# mainboard_interface_v1_5.net
KiCad netlist of a schematic drawn in Altium Designer
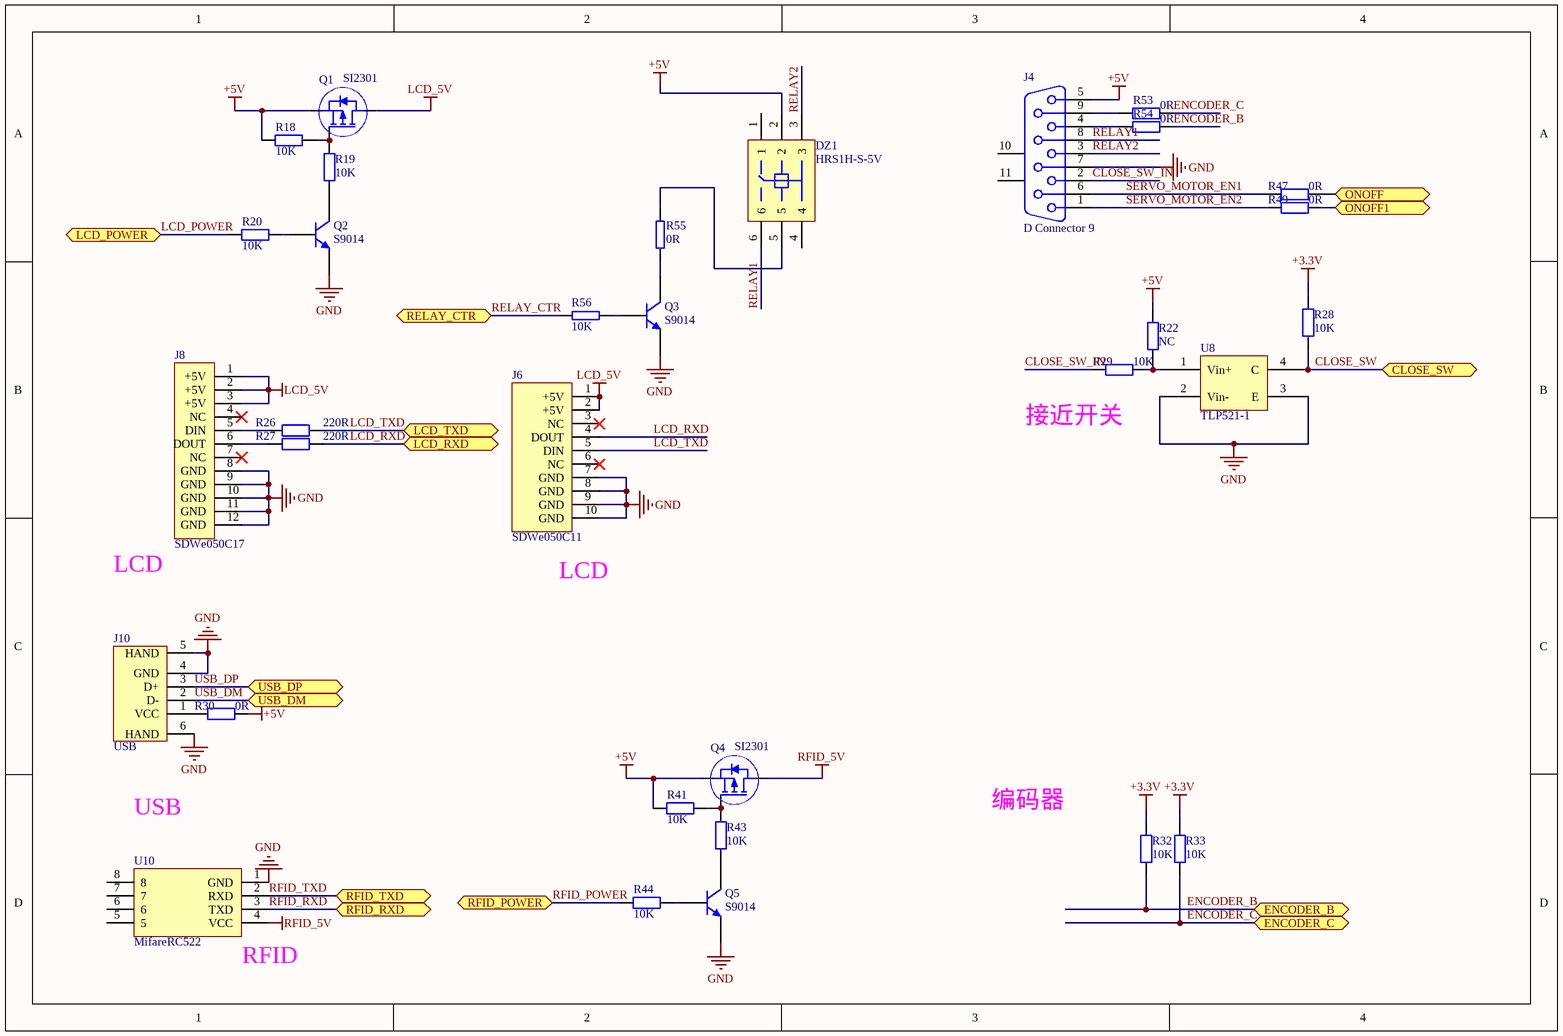
[diagram p0: mainboard_interface.v1.5.SchDoc]

(export (version "E")
  (design (tool "Eeschema 10.0.6"))
  (components
    (comp (ref "DZ1")
      (value "HRS1H-S-5V")
      (footprint "HRS1H-S-DC5")
      (libsource (lib "Componet") (part "HRS1H-S-5V"))
    )
    (comp (ref "J4")
      (value "D Connector 9")
      (footprint "DSUB1.385-2H9")
      (description "Receptacle Assembly, 9 Position, Right Angle")
      (fields (field (name "PUBLISHER") "Altium Limited"))
      (libsource (lib "Miscellaneous Connectors") (part "D Connector 9"))
    )
    (comp (ref "J6")
      (value "SDWe050C11")
      (footprint "8PIN_2.0SMD")
      (libsource (lib "Componet") (part "SDWe043T04"))
    )
    (comp (ref "J8")
      (value "SDWe050C17")
      (footprint "FCC1.0-10")
      (libsource (lib "Connector") (part "SH-12"))
    )
    (comp (ref "J10") (value "USB") (footprint "USB_FEMALE_A") (libsource (lib "Connector") (part "USB")))
    (comp (ref "Q1") (value "SI2301") (footprint "MOS-N_SOT-23") (libsource (lib "*") (part "MOS-P_SOT-23")))
    (comp (ref "Q2") (value "S9014") (footprint "901X_SOT-23") (libsource (lib "Componet") (part "NPN")))
    (comp (ref "Q3") (value "S9014") (footprint "901X_SOT-23") (libsource (lib "Componet") (part "NPN")))
    (comp (ref "Q4") (value "SI2301") (footprint "MOS-N_SOT-23") (libsource (lib "*") (part "MOS-P_SOT-23")))
    (comp (ref "Q5") (value "S9014") (footprint "901X_SOT-23") (libsource (lib "Componet") (part "NPN")))
    (comp (ref "R18")
      (value "10K")
      (footprint "0805")
      (description "Resistor")
      (fields (field (name "PUBLISHER") "Altium Limited"))
      (libsource (lib "") (part "Res2_1"))
    )
    (comp (ref "R19")
      (value "10K")
      (footprint "0805")
      (description "Resistor")
      (fields (field (name "PUBLISHER") "Altium Limited"))
      (libsource (lib "") (part "Res2_2"))
    )
    (comp (ref "R20")
      (value "10K")
      (footprint "0805")
      (description "Resistor")
      (fields (field (name "PUBLISHER") "Altium Limited"))
      (libsource (lib "") (part "Res2_1"))
    )
    (comp (ref "R22")
      (value "NC")
      (footprint "0805")
      (description "Resistor")
      (fields (field (name "PUBLISHER") "Altium Limited"))
      (libsource (lib "") (part "Res2_3"))
    )
    (comp (ref "R26")
      (value "220R")
      (footprint "0805")
      (description "Resistor")
      (fields (field (name "PUBLISHER") "Altium Limited"))
      (libsource (lib "") (part "Res2_1"))
    )
    (comp (ref "R27")
      (value "220R")
      (footprint "0805")
      (description "Resistor")
      (fields (field (name "PUBLISHER") "Altium Limited"))
      (libsource (lib "") (part "Res2_1"))
    )
    (comp (ref "R28")
      (value "10K")
      (footprint "0805")
      (description "Resistor")
      (fields (field (name "PUBLISHER") "Altium Limited"))
      (libsource (lib "") (part "Res2_3"))
    )
    (comp (ref "R29")
      (value "10K")
      (footprint "0805")
      (description "Resistor")
      (fields (field (name "PUBLISHER") "Altium Limited"))
      (libsource (lib "TIAN's Schlib") (part "Res2"))
    )
    (comp (ref "R30")
      (value "0R")
      (footprint "0805")
      (description "Resistor")
      (fields (field (name "PUBLISHER") "Altium Limited"))
      (libsource (lib "TIAN's Schlib") (part "Res2"))
    )
    (comp (ref "R32")
      (value "10K")
      (footprint "0805")
      (description "Resistor")
      (fields (field (name "PUBLISHER") "Altium Limited"))
      (libsource (lib "") (part "Res2_3"))
    )
    (comp (ref "R33")
      (value "10K")
      (footprint "0805")
      (description "Resistor")
      (fields (field (name "PUBLISHER") "Altium Limited"))
      (libsource (lib "") (part "Res2_3"))
    )
    (comp (ref "R41")
      (value "10K")
      (footprint "0805")
      (description "Resistor")
      (fields (field (name "PUBLISHER") "Altium Limited"))
      (libsource (lib "") (part "Res2_1"))
    )
    (comp (ref "R43")
      (value "10K")
      (footprint "0805")
      (description "Resistor")
      (fields (field (name "PUBLISHER") "Altium Limited"))
      (libsource (lib "") (part "Res2_2"))
    )
    (comp (ref "R44")
      (value "10K")
      (footprint "0805")
      (description "Resistor")
      (fields (field (name "PUBLISHER") "Altium Limited"))
      (libsource (lib "") (part "Res2_1"))
    )
    (comp (ref "R47")
      (value "0R")
      (footprint "0805")
      (description "Resistor")
      (fields (field (name "PUBLISHER") "Altium Limited"))
      (libsource (lib "TIAN's Schlib") (part "Res2"))
    )
    (comp (ref "R49")
      (value "0R")
      (footprint "0805")
      (description "Resistor")
      (fields (field (name "PUBLISHER") "Altium Limited"))
      (libsource (lib "TIAN's Schlib") (part "Res2"))
    )
    (comp (ref "R53")
      (value "0R")
      (footprint "0805")
      (description "Resistor")
      (fields (field (name "PUBLISHER") "Altium Limited"))
      (libsource (lib "") (part "Res2_1"))
    )
    (comp (ref "R54")
      (value "0R")
      (footprint "0805")
      (description "Resistor")
      (fields (field (name "PUBLISHER") "Altium Limited"))
      (libsource (lib "") (part "Res2_1"))
    )
    (comp (ref "R55")
      (value "0R")
      (footprint "0805")
      (description "电阻")
      (libsource (lib "Component") (part "RES"))
    )
    (comp (ref "R56")
      (value "10K")
      (footprint "0805")
      (description "电阻")
      (libsource (lib "Component") (part "RES"))
    )
    (comp (ref "U8") (value "TLP521-1") (footprint "TLP521-1") (libsource (lib "Chip") (part "TLP521-1")))
    (comp (ref "U10")
      (value "MifareRC522")
      (footprint "MifareRC522")
      (libsource (lib "Componet") (part "MifareRC522"))
    )
  )
  (nets
    (net (code "1") (name "+3.3V") (class "Default")
      (node (ref "R28") (pin "1") (pinfunction "1_1") (pintype "passive"))
      (node (ref "R32") (pin "1") (pinfunction "1_1") (pintype "passive"))
      (node (ref "R33") (pin "1") (pinfunction "1_1") (pintype "passive"))
    )
    (net (code "2") (name "+5V") (class "Default")
      (node (ref "DZ1") (pin "2") (pinfunction "2_2") (pintype "passive"))
      (node (ref "J4") (pin "5") (pinfunction "5_5") (pintype "passive"))
      (node (ref "Q1") (pin "S") (pinfunction "S_S") (pintype "passive"))
      (node (ref "Q4") (pin "S") (pinfunction "S_S") (pintype "passive"))
      (node (ref "R18") (pin "1") (pinfunction "1_1") (pintype "passive"))
      (node (ref "R22") (pin "1") (pinfunction "1_1") (pintype "passive"))
      (node (ref "R30") (pin "1") (pinfunction "1_1") (pintype "passive"))
      (node (ref "R41") (pin "1") (pinfunction "1_1") (pintype "passive"))
    )
    (net (code "3") (name "/CLOSE_SW") (class "Default")
      (node (ref "R28") (pin "2") (pinfunction "2_2") (pintype "passive"))
      (node (ref "U8") (pin "4") (pinfunction "C_4") (pintype "passive"))
    )
    (net (code "4") (name "/CLOSE_SW_IN") (class "Default")
      (node (ref "J4") (pin "2") (pinfunction "2_2") (pintype "passive"))
      (node (ref "R29") (pin "2") (pinfunction "2_2") (pintype "passive"))
    )
    (net (code "5") (name "/ENCODER_B") (class "Default")
      (node (ref "R32") (pin "2") (pinfunction "2_2") (pintype "passive"))
      (node (ref "R54") (pin "2") (pinfunction "2_2") (pintype "passive"))
    )
    (net (code "6") (name "/ENCODER_C") (class "Default")
      (node (ref "R33") (pin "2") (pinfunction "2_2") (pintype "passive"))
      (node (ref "R53") (pin "2") (pinfunction "2_2") (pintype "passive"))
    )
    (net (code "7") (name "/LCD_POWER") (class "Default")
      (node (ref "R20") (pin "1") (pinfunction "1_1") (pintype "passive"))
    )
    (net (code "8") (name "/LCD_RXD") (class "Default")
      (node (ref "J6") (pin "4") (pinfunction "DOUT_4") (pintype "passive"))
      (node (ref "R27") (pin "2") (pinfunction "2_2") (pintype "passive"))
    )
    (net (code "9") (name "/LCD_TXD") (class "Default")
      (node (ref "J6") (pin "5") (pinfunction "DIN_5") (pintype "passive"))
      (node (ref "R26") (pin "2") (pinfunction "2_2") (pintype "passive"))
    )
    (net (code "10") (name "/ONOFF") (class "Default")
      (node (ref "R47") (pin "1") (pinfunction "1_1") (pintype "passive"))
    )
    (net (code "11") (name "/ONOFF1") (class "Default")
      (node (ref "R49") (pin "1") (pinfunction "1_1") (pintype "passive"))
    )
    (net (code "12") (name "/RELAY1") (class "Default")
      (node (ref "DZ1") (pin "6") (pinfunction "6_6") (pintype "passive"))
      (node (ref "J4") (pin "8") (pinfunction "8_8") (pintype "passive"))
    )
    (net (code "13") (name "/RELAY2") (class "Default")
      (node (ref "DZ1") (pin "3") (pinfunction "3_3") (pintype "passive"))
      (node (ref "J4") (pin "3") (pinfunction "3_3") (pintype "passive"))
    )
    (net (code "14") (name "/RELAY_CTR") (class "Default")
      (node (ref "R56") (pin "2") (pinfunction "2_2") (pintype "passive"))
    )
    (net (code "15") (name "/RFID_POWER") (class "Default")
      (node (ref "R44") (pin "1") (pinfunction "1_1") (pintype "passive"))
    )
    (net (code "16") (name "/RFID_RXD") (class "Default")
      (node (ref "U10") (pin "3") (pinfunction "TXD_3") (pintype "passive"))
    )
    (net (code "17") (name "/RFID_TXD") (class "Default")
      (node (ref "U10") (pin "2") (pinfunction "RXD_2") (pintype "passive"))
    )
    (net (code "18") (name "/SERVO_MOTOR_EN1") (class "Default")
      (node (ref "J4") (pin "6") (pinfunction "6_6") (pintype "passive"))
      (node (ref "R47") (pin "2") (pinfunction "2_2") (pintype "passive"))
    )
    (net (code "19") (name "/SERVO_MOTOR_EN2") (class "Default")
      (node (ref "J4") (pin "1") (pinfunction "1_1") (pintype "passive"))
      (node (ref "R49") (pin "2") (pinfunction "2_2") (pintype "passive"))
    )
    (net (code "20") (name "/USB_DM") (class "Default")
      (node (ref "J10") (pin "2") (pinfunction "D-_2") (pintype "passive"))
    )
    (net (code "21") (name "/USB_DP") (class "Default")
      (node (ref "J10") (pin "3") (pinfunction "D+_3") (pintype "passive"))
    )
    (net (code "22") (name "GND") (class "Default")
      (node (ref "J10") (pin "4") (pinfunction "GND_4") (pintype "passive"))
      (node (ref "J10") (pin "5") (pinfunction "HAND_5") (pintype "passive"))
      (node (ref "J10") (pin "6") (pinfunction "HAND_6") (pintype "passive"))
      (node (ref "J4") (pin "7") (pinfunction "7_7") (pintype "passive"))
      (node (ref "J6") (pin "10") (pinfunction "GND_10") (pintype "passive"))
      (node (ref "J6") (pin "7") (pinfunction "GND_7") (pintype "passive"))
      (node (ref "J6") (pin "8") (pinfunction "GND_8") (pintype "passive"))
      (node (ref "J6") (pin "9") (pinfunction "GND_9") (pintype "passive"))
      (node (ref "J8") (pin "10") (pinfunction "GND_10") (pintype "passive"))
      (node (ref "J8") (pin "11") (pinfunction "GND_11") (pintype "passive"))
      (node (ref "J8") (pin "12") (pinfunction "GND_12") (pintype "passive"))
      (node (ref "J8") (pin "8") (pinfunction "GND_8") (pintype "passive"))
      (node (ref "J8") (pin "9") (pinfunction "GND_9") (pintype "passive"))
      (node (ref "Q2") (pin "3") (pinfunction "E_3") (pintype "passive"))
      (node (ref "Q3") (pin "3") (pinfunction "E_3") (pintype "passive"))
      (node (ref "Q5") (pin "3") (pinfunction "E_3") (pintype "passive"))
      (node (ref "U10") (pin "1") (pinfunction "GND_1") (pintype "passive"))
      (node (ref "U8") (pin "2") (pinfunction "Vin-_2") (pintype "passive"))
      (node (ref "U8") (pin "3") (pinfunction "E_3") (pintype "passive"))
    )
    (net (code "23") (name "LCD_5V") (class "Default")
      (node (ref "J6") (pin "1") (pinfunction "+5V_1") (pintype "passive"))
      (node (ref "J6") (pin "2") (pinfunction "+5V_2") (pintype "passive"))
      (node (ref "J8") (pin "1") (pinfunction "+5V_1") (pintype "passive"))
      (node (ref "J8") (pin "2") (pinfunction "+5V_2") (pintype "passive"))
      (node (ref "J8") (pin "3") (pinfunction "+5V_3") (pintype "passive"))
      (node (ref "Q1") (pin "D") (pinfunction "D_D") (pintype "passive"))
    )
    (net (code "24") (name "Net-(DZ1-Pad5)") (class "Default")
      (node (ref "DZ1") (pin "5") (pinfunction "5_5") (pintype "passive"))
      (node (ref "R55") (pin "2") (pinfunction "2_2") (pintype "passive"))
    )
    (net (code "25") (name "Net-(J4-Pad4)") (class "Default")
      (node (ref "J4") (pin "4") (pinfunction "4_4") (pintype "passive"))
      (node (ref "R54") (pin "1") (pinfunction "1_1") (pintype "passive"))
    )
    (net (code "26") (name "Net-(J4-Pad9)") (class "Default")
      (node (ref "J4") (pin "9") (pinfunction "9_9") (pintype "passive"))
      (node (ref "R53") (pin "1") (pinfunction "1_1") (pintype "passive"))
    )
    (net (code "27") (name "Net-(J8-DIN)") (class "Default")
      (node (ref "J8") (pin "5") (pinfunction "DIN_5") (pintype "passive"))
      (node (ref "R26") (pin "1") (pinfunction "1_1") (pintype "passive"))
    )
    (net (code "28") (name "Net-(J8-DOUT)") (class "Default")
      (node (ref "J8") (pin "6") (pinfunction "DOUT_6") (pintype "passive"))
      (node (ref "R27") (pin "1") (pinfunction "1_1") (pintype "passive"))
    )
    (net (code "29") (name "Net-(J10-VCC)") (class "Default")
      (node (ref "J10") (pin "1") (pinfunction "VCC_1") (pintype "passive"))
      (node (ref "R30") (pin "2") (pinfunction "2_2") (pintype "passive"))
    )
    (net (code "30") (name "Net-(Q1-PadG)") (class "Default")
      (node (ref "Q1") (pin "G") (pinfunction "G_G") (pintype "passive"))
      (node (ref "R18") (pin "2") (pinfunction "2_2") (pintype "passive"))
      (node (ref "R19") (pin "2") (pinfunction "2_2") (pintype "passive"))
    )
    (net (code "31") (name "Net-(Q2-B)") (class "Default")
      (node (ref "Q2") (pin "2") (pinfunction "B_2") (pintype "passive"))
      (node (ref "R20") (pin "2") (pinfunction "2_2") (pintype "passive"))
    )
    (net (code "32") (name "Net-(Q2-C)") (class "Default")
      (node (ref "Q2") (pin "1") (pinfunction "C_1") (pintype "passive"))
      (node (ref "R19") (pin "1") (pinfunction "1_1") (pintype "passive"))
    )
    (net (code "33") (name "Net-(Q3-B)") (class "Default")
      (node (ref "Q3") (pin "2") (pinfunction "B_2") (pintype "passive"))
      (node (ref "R56") (pin "1") (pinfunction "1_1") (pintype "passive"))
    )
    (net (code "34") (name "Net-(Q3-C)") (class "Default")
      (node (ref "Q3") (pin "1") (pinfunction "C_1") (pintype "passive"))
      (node (ref "R55") (pin "1") (pinfunction "1_1") (pintype "passive"))
    )
    (net (code "35") (name "Net-(Q4-PadG)") (class "Default")
      (node (ref "Q4") (pin "G") (pinfunction "G_G") (pintype "passive"))
      (node (ref "R41") (pin "2") (pinfunction "2_2") (pintype "passive"))
      (node (ref "R43") (pin "2") (pinfunction "2_2") (pintype "passive"))
    )
    (net (code "36") (name "Net-(Q5-B)") (class "Default")
      (node (ref "Q5") (pin "2") (pinfunction "B_2") (pintype "passive"))
      (node (ref "R44") (pin "2") (pinfunction "2_2") (pintype "passive"))
    )
    (net (code "37") (name "Net-(Q5-C)") (class "Default")
      (node (ref "Q5") (pin "1") (pinfunction "C_1") (pintype "passive"))
      (node (ref "R43") (pin "1") (pinfunction "1_1") (pintype "passive"))
    )
    (net (code "38") (name "Net-(U8-Vin+)") (class "Default")
      (node (ref "R22") (pin "2") (pinfunction "2_2") (pintype "passive"))
      (node (ref "R29") (pin "1") (pinfunction "1_1") (pintype "passive"))
      (node (ref "U8") (pin "1") (pinfunction "Vin+_1") (pintype "passive"))
    )
    (net (code "39") (name "RFID_5V") (class "Default")
      (node (ref "Q4") (pin "D") (pinfunction "D_D") (pintype "passive"))
      (node (ref "U10") (pin "4") (pinfunction "VCC_4") (pintype "passive"))
    )
    (net (code "40") (name "unconnected-(DZ1-Pad1)") (class "Default")
      (node (ref "DZ1") (pin "1") (pinfunction "1_1") (pintype "passive"))
    )
    (net (code "41") (name "unconnected-(DZ1-Pad4)") (class "Default")
      (node (ref "DZ1") (pin "4") (pinfunction "4_4") (pintype "passive"))
    )
    (net (code "42") (name "unconnected-(J4-MH1-Pad10)") (class "Default")
      (node (ref "J4") (pin "10") (pinfunction "MH1_10") (pintype "passive"))
    )
    (net (code "43") (name "unconnected-(J4-MH2-Pad11)") (class "Default")
      (node (ref "J4") (pin "11") (pinfunction "MH2_11") (pintype "passive"))
    )
    (net (code "44") (name "unconnected-(J6-NC-Pad3)") (class "Default")
      (node (ref "J6") (pin "3") (pinfunction "NC_3") (pintype "passive+no_connect"))
    )
    (net (code "45") (name "unconnected-(J6-NC-Pad6)") (class "Default")
      (node (ref "J6") (pin "6") (pinfunction "NC_6") (pintype "passive+no_connect"))
    )
    (net (code "46") (name "unconnected-(J8-NC-Pad4)") (class "Default")
      (node (ref "J8") (pin "4") (pinfunction "NC_4") (pintype "passive+no_connect"))
    )
    (net (code "47") (name "unconnected-(J8-NC-Pad7)") (class "Default")
      (node (ref "J8") (pin "7") (pinfunction "NC_7") (pintype "passive+no_connect"))
    )
    (net (code "48") (name "unconnected-(U10-Pad5)") (class "Default")
      (node (ref "U10") (pin "5") (pinfunction "5_5") (pintype "passive"))
    )
    (net (code "49") (name "unconnected-(U10-Pad6)") (class "Default")
      (node (ref "U10") (pin "6") (pinfunction "6_6") (pintype "passive"))
    )
    (net (code "50") (name "unconnected-(U10-Pad7)") (class "Default")
      (node (ref "U10") (pin "7") (pinfunction "7_7") (pintype "passive"))
    )
    (net (code "51") (name "unconnected-(U10-Pad8)") (class "Default")
      (node (ref "U10") (pin "8") (pinfunction "8_8") (pintype "passive"))
    )
  )
)
